# 12-AM64x-01.net
KiCad netlist of a schematic drawn in Altium Designer
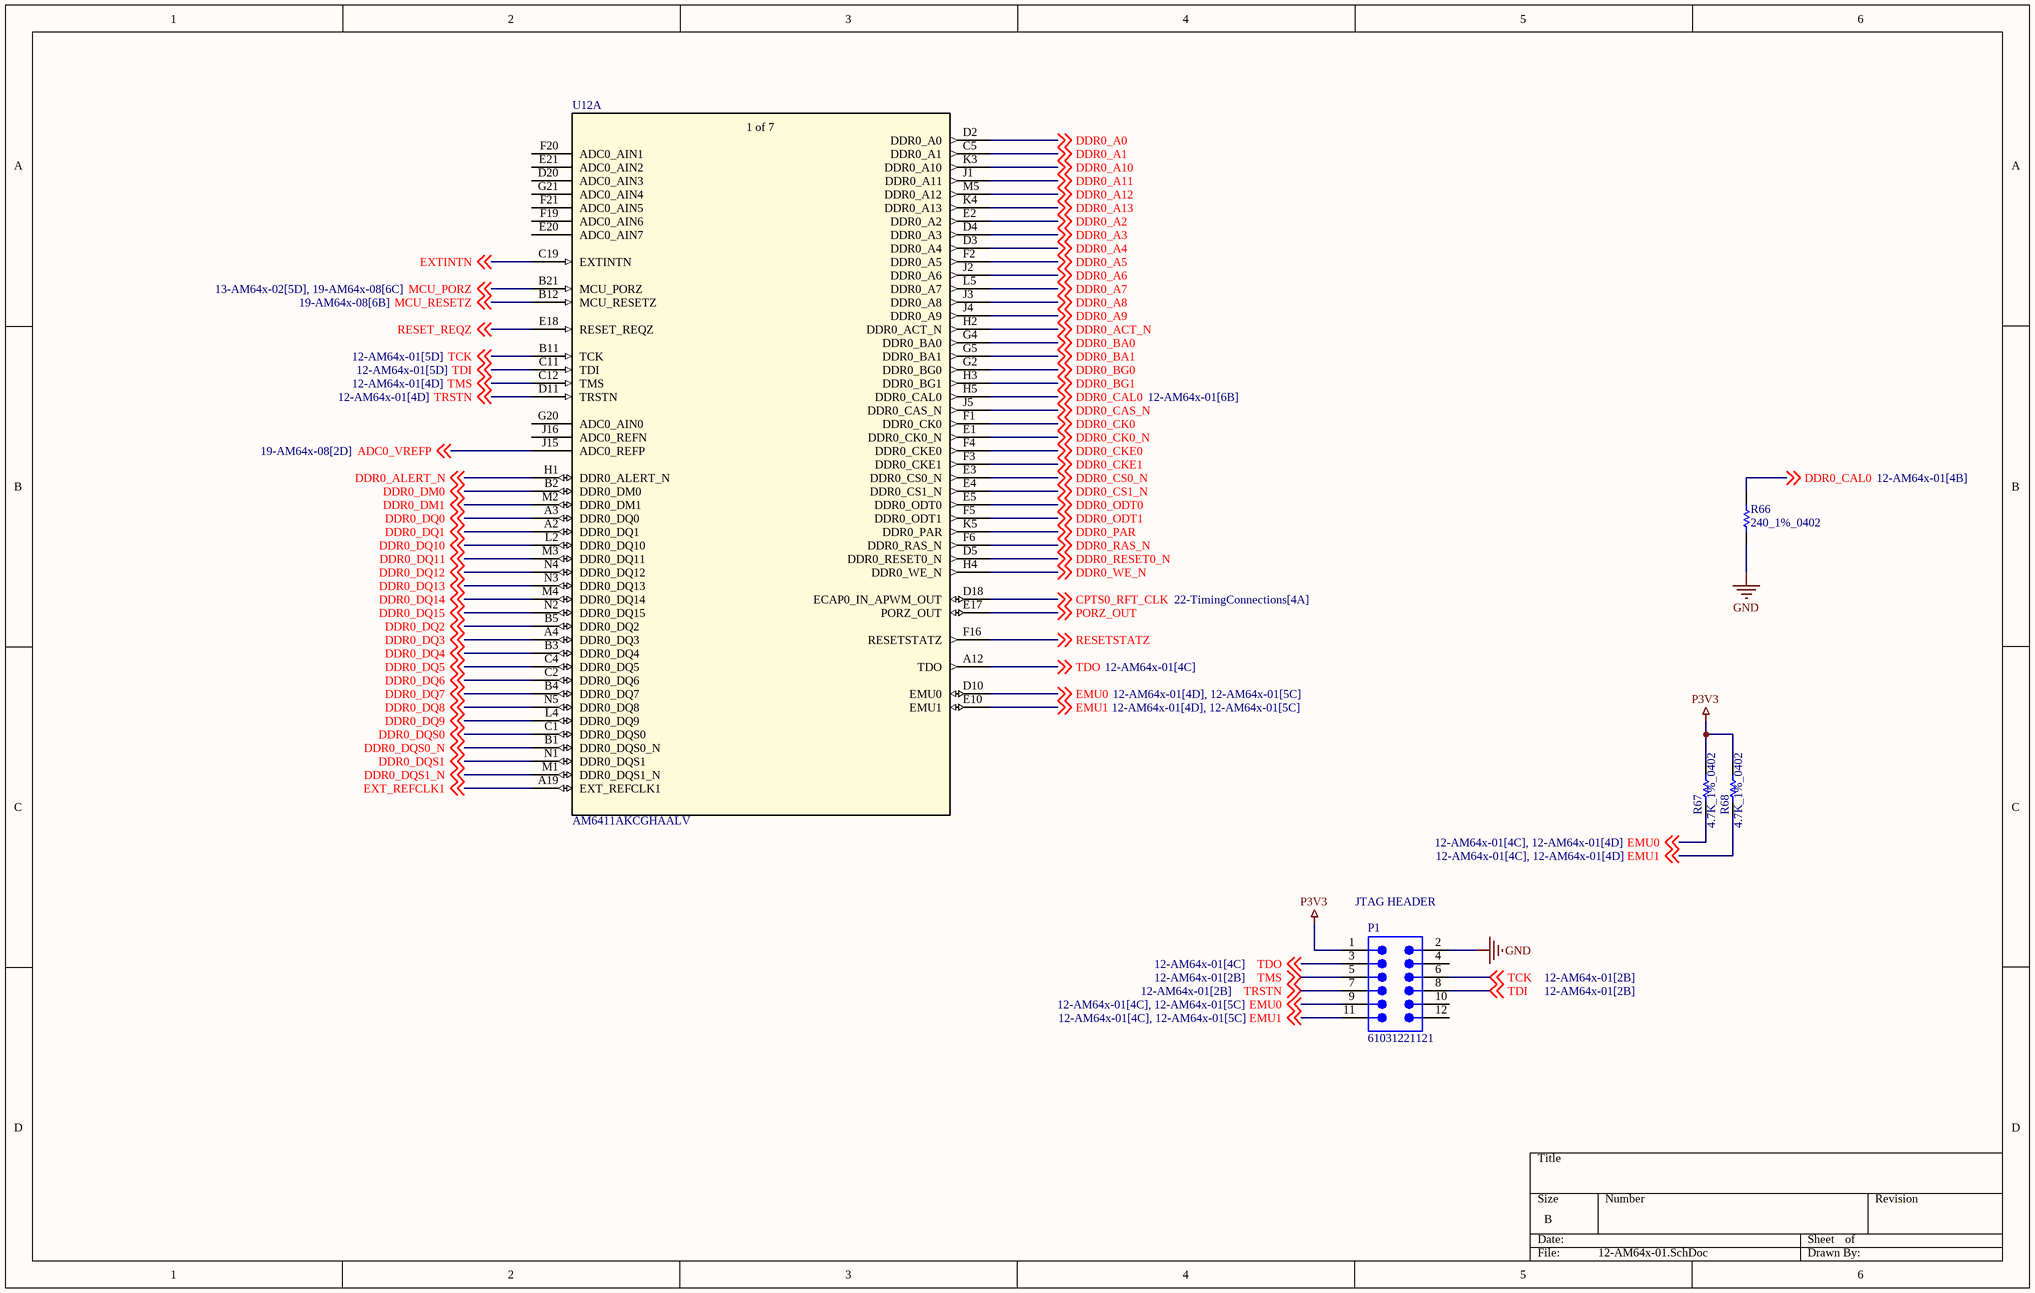
[diagram p0: 12-AM64x-01.SchDoc]

(export (version "E")
  (design (tool "Eeschema 10.0.6"))
  (components
    (comp (ref "P1")
      (value "61031221121")
      (footprint "61031221121")
      (libsource (lib "Altium Content Vault") (part "Header_Male_2R_12P"))
    )
    (comp (ref "R66")
      (value "240_1%_0402")
      (footprint "RESC1005X40X25ML05T05")
      (fields (field (name "MANUFACTURER") "Vishay Dale") (field (name "PART NUMBER") "CRCW0402240RFKED"))
      (libsource (lib "Altium Content Vault") (part "RES"))
    )
    (comp (ref "R67")
      (value "4.7K_1%_0402")
      (footprint "RESC1005X40X25NL10T10")
      (fields (field (name "MANUFACTURER") "Bourns") (field (name "PART NUMBER") "CR0402-FX-4701GLF"))
      (libsource (lib "Altium Content Vault") (part "RES"))
    )
    (comp (ref "R68")
      (value "4.7K_1%_0402")
      (footprint "RESC1005X40X25NL10T10")
      (fields (field (name "MANUFACTURER") "Bourns") (field (name "PART NUMBER") "CR0402-FX-4701GLF"))
      (libsource (lib "Altium Content Vault") (part "RES"))
    )
    (comp (ref "U12")
      (value "AM6411AKCGHAALV")
      (footprint "FCBGA441_ALV_TEX")
      (description "No Description Available")
      (libsource (lib "AM6411AKCGHAALV") (part "AM6411AKCGHAALV"))
    )
  )
  (nets
    (net (code "1") (name "ADC0_VREFP") (class "Default")
      (node (ref "U12") (pin "J15") (pinfunction "ADC0_REFP_J15") (pintype "passive"))
    )
    (net (code "2") (name "CPTS0_RFT_CLK") (class "Default")
      (node (ref "U12") (pin "D18") (pinfunction "ECAP0_IN_APWM_OUT_D18") (pintype "bidirectional"))
    )
    (net (code "3") (name "DDR0_A0") (class "Default")
      (node (ref "U12") (pin "D2") (pinfunction "DDR0_A0_D2") (pintype "output"))
    )
    (net (code "4") (name "DDR0_A1") (class "Default")
      (node (ref "U12") (pin "C5") (pinfunction "DDR0_A1_C5") (pintype "output"))
    )
    (net (code "5") (name "DDR0_A2") (class "Default")
      (node (ref "U12") (pin "E2") (pinfunction "DDR0_A2_E2") (pintype "output"))
    )
    (net (code "6") (name "DDR0_A3") (class "Default")
      (node (ref "U12") (pin "D4") (pinfunction "DDR0_A3_D4") (pintype "output"))
    )
    (net (code "7") (name "DDR0_A4") (class "Default")
      (node (ref "U12") (pin "D3") (pinfunction "DDR0_A4_D3") (pintype "output"))
    )
    (net (code "8") (name "DDR0_A5") (class "Default")
      (node (ref "U12") (pin "F2") (pinfunction "DDR0_A5_F2") (pintype "output"))
    )
    (net (code "9") (name "DDR0_A6") (class "Default")
      (node (ref "U12") (pin "J2") (pinfunction "DDR0_A6_J2") (pintype "output"))
    )
    (net (code "10") (name "DDR0_A7") (class "Default")
      (node (ref "U12") (pin "L5") (pinfunction "DDR0_A7_L5") (pintype "output"))
    )
    (net (code "11") (name "DDR0_A8") (class "Default")
      (node (ref "U12") (pin "J3") (pinfunction "DDR0_A8_J3") (pintype "output"))
    )
    (net (code "12") (name "DDR0_A9") (class "Default")
      (node (ref "U12") (pin "J4") (pinfunction "DDR0_A9_J4") (pintype "output"))
    )
    (net (code "13") (name "DDR0_A10") (class "Default")
      (node (ref "U12") (pin "K3") (pinfunction "DDR0_A10_K3") (pintype "output"))
    )
    (net (code "14") (name "DDR0_A11") (class "Default")
      (node (ref "U12") (pin "J1") (pinfunction "DDR0_A11_J1") (pintype "output"))
    )
    (net (code "15") (name "DDR0_A12") (class "Default")
      (node (ref "U12") (pin "M5") (pinfunction "DDR0_A12_M5") (pintype "output"))
    )
    (net (code "16") (name "DDR0_A13") (class "Default")
      (node (ref "U12") (pin "K4") (pinfunction "DDR0_A13_K4") (pintype "output"))
    )
    (net (code "17") (name "DDR0_ACT_N") (class "Default")
      (node (ref "U12") (pin "H2") (pinfunction "DDR0_ACT_N_H2") (pintype "output"))
    )
    (net (code "18") (name "DDR0_ALERT_N") (class "Default")
      (node (ref "U12") (pin "H1") (pinfunction "DDR0_ALERT_N_H1") (pintype "bidirectional"))
    )
    (net (code "19") (name "DDR0_BA0") (class "Default")
      (node (ref "U12") (pin "G4") (pinfunction "DDR0_BA0_G4") (pintype "output"))
    )
    (net (code "20") (name "DDR0_BA1") (class "Default")
      (node (ref "U12") (pin "G5") (pinfunction "DDR0_BA1_G5") (pintype "output"))
    )
    (net (code "21") (name "DDR0_BG0") (class "Default")
      (node (ref "U12") (pin "G2") (pinfunction "DDR0_BG0_G2") (pintype "output"))
    )
    (net (code "22") (name "DDR0_BG1") (class "Default")
      (node (ref "U12") (pin "H3") (pinfunction "DDR0_BG1_H3") (pintype "output"))
    )
    (net (code "23") (name "DDR0_CAL0") (class "Default")
      (node (ref "R66") (pin "2") (pinfunction "2_2") (pintype "passive"))
      (node (ref "U12") (pin "H5") (pinfunction "DDR0_CAL0_H5") (pintype "output"))
    )
    (net (code "24") (name "DDR0_CAS_N") (class "Default")
      (node (ref "U12") (pin "J5") (pinfunction "DDR0_CAS_N_J5") (pintype "output"))
    )
    (net (code "25") (name "DDR0_CK0") (class "Default")
      (node (ref "U12") (pin "F1") (pinfunction "DDR0_CK0_F1") (pintype "output"))
    )
    (net (code "26") (name "DDR0_CK0_N") (class "Default")
      (node (ref "U12") (pin "E1") (pinfunction "DDR0_CK0_N_E1") (pintype "output"))
    )
    (net (code "27") (name "DDR0_CKE0") (class "Default")
      (node (ref "U12") (pin "F4") (pinfunction "DDR0_CKE0_F4") (pintype "output"))
    )
    (net (code "28") (name "DDR0_CKE1") (class "Default")
      (node (ref "U12") (pin "F3") (pinfunction "DDR0_CKE1_F3") (pintype "output"))
    )
    (net (code "29") (name "DDR0_CS0_N") (class "Default")
      (node (ref "U12") (pin "E3") (pinfunction "DDR0_CS0_N_E3") (pintype "output"))
    )
    (net (code "30") (name "DDR0_CS1_N") (class "Default")
      (node (ref "U12") (pin "E4") (pinfunction "DDR0_CS1_N_E4") (pintype "output"))
    )
    (net (code "31") (name "DDR0_DM0") (class "Default")
      (node (ref "U12") (pin "B2") (pinfunction "DDR0_DM0_B2") (pintype "bidirectional"))
    )
    (net (code "32") (name "DDR0_DM1") (class "Default")
      (node (ref "U12") (pin "M2") (pinfunction "DDR0_DM1_M2") (pintype "bidirectional"))
    )
    (net (code "33") (name "DDR0_DQ0") (class "Default")
      (node (ref "U12") (pin "A3") (pinfunction "DDR0_DQ0_A3") (pintype "bidirectional"))
    )
    (net (code "34") (name "DDR0_DQ1") (class "Default")
      (node (ref "U12") (pin "A2") (pinfunction "DDR0_DQ1_A2") (pintype "bidirectional"))
    )
    (net (code "35") (name "DDR0_DQ2") (class "Default")
      (node (ref "U12") (pin "B5") (pinfunction "DDR0_DQ2_B5") (pintype "bidirectional"))
    )
    (net (code "36") (name "DDR0_DQ3") (class "Default")
      (node (ref "U12") (pin "A4") (pinfunction "DDR0_DQ3_A4") (pintype "bidirectional"))
    )
    (net (code "37") (name "DDR0_DQ4") (class "Default")
      (node (ref "U12") (pin "B3") (pinfunction "DDR0_DQ4_B3") (pintype "bidirectional"))
    )
    (net (code "38") (name "DDR0_DQ5") (class "Default")
      (node (ref "U12") (pin "C4") (pinfunction "DDR0_DQ5_C4") (pintype "bidirectional"))
    )
    (net (code "39") (name "DDR0_DQ6") (class "Default")
      (node (ref "U12") (pin "C2") (pinfunction "DDR0_DQ6_C2") (pintype "bidirectional"))
    )
    (net (code "40") (name "DDR0_DQ7") (class "Default")
      (node (ref "U12") (pin "B4") (pinfunction "DDR0_DQ7_B4") (pintype "bidirectional"))
    )
    (net (code "41") (name "DDR0_DQ8") (class "Default")
      (node (ref "U12") (pin "N5") (pinfunction "DDR0_DQ8_N5") (pintype "bidirectional"))
    )
    (net (code "42") (name "DDR0_DQ9") (class "Default")
      (node (ref "U12") (pin "L4") (pinfunction "DDR0_DQ9_L4") (pintype "bidirectional"))
    )
    (net (code "43") (name "DDR0_DQ10") (class "Default")
      (node (ref "U12") (pin "L2") (pinfunction "DDR0_DQ10_L2") (pintype "bidirectional"))
    )
    (net (code "44") (name "DDR0_DQ11") (class "Default")
      (node (ref "U12") (pin "M3") (pinfunction "DDR0_DQ11_M3") (pintype "bidirectional"))
    )
    (net (code "45") (name "DDR0_DQ12") (class "Default")
      (node (ref "U12") (pin "N4") (pinfunction "DDR0_DQ12_N4") (pintype "bidirectional"))
    )
    (net (code "46") (name "DDR0_DQ13") (class "Default")
      (node (ref "U12") (pin "N3") (pinfunction "DDR0_DQ13_N3") (pintype "bidirectional"))
    )
    (net (code "47") (name "DDR0_DQ14") (class "Default")
      (node (ref "U12") (pin "M4") (pinfunction "DDR0_DQ14_M4") (pintype "bidirectional"))
    )
    (net (code "48") (name "DDR0_DQ15") (class "Default")
      (node (ref "U12") (pin "N2") (pinfunction "DDR0_DQ15_N2") (pintype "bidirectional"))
    )
    (net (code "49") (name "DDR0_DQS0") (class "Default")
      (node (ref "U12") (pin "C1") (pinfunction "DDR0_DQS0_C1") (pintype "bidirectional"))
    )
    (net (code "50") (name "DDR0_DQS0_N") (class "Default")
      (node (ref "U12") (pin "B1") (pinfunction "DDR0_DQS0_N_B1") (pintype "bidirectional"))
    )
    (net (code "51") (name "DDR0_DQS1") (class "Default")
      (node (ref "U12") (pin "N1") (pinfunction "DDR0_DQS1_N1") (pintype "bidirectional"))
    )
    (net (code "52") (name "DDR0_DQS1_N") (class "Default")
      (node (ref "U12") (pin "M1") (pinfunction "DDR0_DQS1_N_M1") (pintype "bidirectional"))
    )
    (net (code "53") (name "DDR0_ODT0") (class "Default")
      (node (ref "U12") (pin "E5") (pinfunction "DDR0_ODT0_E5") (pintype "output"))
    )
    (net (code "54") (name "DDR0_ODT1") (class "Default")
      (node (ref "U12") (pin "F5") (pinfunction "DDR0_ODT1_F5") (pintype "output"))
    )
    (net (code "55") (name "DDR0_PAR") (class "Default")
      (node (ref "U12") (pin "K5") (pinfunction "DDR0_PAR_K5") (pintype "output"))
    )
    (net (code "56") (name "DDR0_RAS_N") (class "Default")
      (node (ref "U12") (pin "F6") (pinfunction "DDR0_RAS_N_F6") (pintype "output"))
    )
    (net (code "57") (name "DDR0_RESET0_N") (class "Default")
      (node (ref "U12") (pin "D5") (pinfunction "DDR0_RESET0_N_D5") (pintype "output"))
    )
    (net (code "58") (name "DDR0_WE_N") (class "Default")
      (node (ref "U12") (pin "H4") (pinfunction "DDR0_WE_N_H4") (pintype "output"))
    )
    (net (code "59") (name "EMU0") (class "Default")
      (node (ref "P1") (pin "9") (pinfunction "9_9") (pintype "passive"))
      (node (ref "R67") (pin "2") (pinfunction "2_2") (pintype "passive"))
      (node (ref "U12") (pin "D10") (pinfunction "EMU0_D10") (pintype "bidirectional"))
    )
    (net (code "60") (name "EMU1") (class "Default")
      (node (ref "P1") (pin "11") (pinfunction "11_11") (pintype "passive"))
      (node (ref "R68") (pin "2") (pinfunction "2_2") (pintype "passive"))
      (node (ref "U12") (pin "E10") (pinfunction "EMU1_E10") (pintype "bidirectional"))
    )
    (net (code "61") (name "EXTINTN") (class "Default")
      (node (ref "U12") (pin "C19") (pinfunction "EXTINTN_C19") (pintype "input"))
    )
    (net (code "62") (name "EXT_REFCLK1") (class "Default")
      (node (ref "U12") (pin "A19") (pinfunction "EXT_REFCLK1_A19") (pintype "bidirectional"))
    )
    (net (code "63") (name "GND") (class "Default")
      (node (ref "P1") (pin "2") (pinfunction "2_2") (pintype "passive"))
      (node (ref "R66") (pin "1") (pinfunction "1_1") (pintype "passive"))
    )
    (net (code "64") (name "MCU_PORZ") (class "Default")
      (node (ref "U12") (pin "B21") (pinfunction "MCU_PORZ_B21") (pintype "input"))
    )
    (net (code "65") (name "MCU_RESETZ") (class "Default")
      (node (ref "U12") (pin "B12") (pinfunction "MCU_RESETZ_B12") (pintype "input"))
    )
    (net (code "66") (name "P3V3") (class "Default")
      (node (ref "P1") (pin "1") (pinfunction "1_1") (pintype "passive"))
      (node (ref "R67") (pin "1") (pinfunction "1_1") (pintype "passive"))
      (node (ref "R68") (pin "1") (pinfunction "1_1") (pintype "passive"))
    )
    (net (code "67") (name "PORZ_OUT") (class "Default")
      (node (ref "U12") (pin "E17") (pinfunction "PORZ_OUT_E17") (pintype "bidirectional"))
    )
    (net (code "68") (name "RESETSTATZ") (class "Default")
      (node (ref "U12") (pin "F16") (pinfunction "RESETSTATZ_F16") (pintype "output"))
    )
    (net (code "69") (name "RESET_REQZ") (class "Default")
      (node (ref "U12") (pin "E18") (pinfunction "RESET_REQZ_E18") (pintype "input"))
    )
    (net (code "70") (name "TCK") (class "Default")
      (node (ref "P1") (pin "6") (pinfunction "6_6") (pintype "passive"))
      (node (ref "U12") (pin "B11") (pinfunction "TCK_B11") (pintype "input"))
    )
    (net (code "71") (name "TDI") (class "Default")
      (node (ref "P1") (pin "8") (pinfunction "8_8") (pintype "passive"))
      (node (ref "U12") (pin "C11") (pinfunction "TDI_C11") (pintype "input"))
    )
    (net (code "72") (name "TDO") (class "Default")
      (node (ref "P1") (pin "3") (pinfunction "3_3") (pintype "passive"))
      (node (ref "U12") (pin "A12") (pinfunction "TDO_A12") (pintype "output"))
    )
    (net (code "73") (name "TMS") (class "Default")
      (node (ref "P1") (pin "5") (pinfunction "5_5") (pintype "passive"))
      (node (ref "U12") (pin "C12") (pinfunction "TMS_C12") (pintype "input"))
    )
    (net (code "74") (name "TRSTN") (class "Default")
      (node (ref "P1") (pin "7") (pinfunction "7_7") (pintype "passive"))
      (node (ref "U12") (pin "D11") (pinfunction "TRSTN_D11") (pintype "input"))
    )
    (net (code "75") (name "unconnected-(P1-Pad4)") (class "Default")
      (node (ref "P1") (pin "4") (pinfunction "4_4") (pintype "passive"))
    )
    (net (code "76") (name "unconnected-(P1-Pad10)") (class "Default")
      (node (ref "P1") (pin "10") (pinfunction "10_10") (pintype "passive"))
    )
    (net (code "77") (name "unconnected-(P1-Pad12)") (class "Default")
      (node (ref "P1") (pin "12") (pinfunction "12_12") (pintype "passive"))
    )
    (net (code "78") (name "unconnected-(U12A-ADC0_AIN0-PadG20)") (class "Default")
      (node (ref "U12") (pin "G20") (pinfunction "ADC0_AIN0_G20") (pintype "passive"))
    )
    (net (code "79") (name "unconnected-(U12A-ADC0_AIN1-PadF20)") (class "Default")
      (node (ref "U12") (pin "F20") (pinfunction "ADC0_AIN1_F20") (pintype "passive"))
    )
    (net (code "80") (name "unconnected-(U12A-ADC0_AIN2-PadE21)") (class "Default")
      (node (ref "U12") (pin "E21") (pinfunction "ADC0_AIN2_E21") (pintype "passive"))
    )
    (net (code "81") (name "unconnected-(U12A-ADC0_AIN3-PadD20)") (class "Default")
      (node (ref "U12") (pin "D20") (pinfunction "ADC0_AIN3_D20") (pintype "passive"))
    )
    (net (code "82") (name "unconnected-(U12A-ADC0_AIN4-PadG21)") (class "Default")
      (node (ref "U12") (pin "G21") (pinfunction "ADC0_AIN4_G21") (pintype "passive"))
    )
    (net (code "83") (name "unconnected-(U12A-ADC0_AIN5-PadF21)") (class "Default")
      (node (ref "U12") (pin "F21") (pinfunction "ADC0_AIN5_F21") (pintype "passive"))
    )
    (net (code "84") (name "unconnected-(U12A-ADC0_AIN6-PadF19)") (class "Default")
      (node (ref "U12") (pin "F19") (pinfunction "ADC0_AIN6_F19") (pintype "passive"))
    )
    (net (code "85") (name "unconnected-(U12A-ADC0_AIN7-PadE20)") (class "Default")
      (node (ref "U12") (pin "E20") (pinfunction "ADC0_AIN7_E20") (pintype "passive"))
    )
    (net (code "86") (name "unconnected-(U12A-ADC0_REFN-PadJ16)") (class "Default")
      (node (ref "U12") (pin "J16") (pinfunction "ADC0_REFN_J16") (pintype "passive"))
    )
  )
)
